# Dumptruck2018.net
KiCad netlist of a schematic drawn in EAGLE
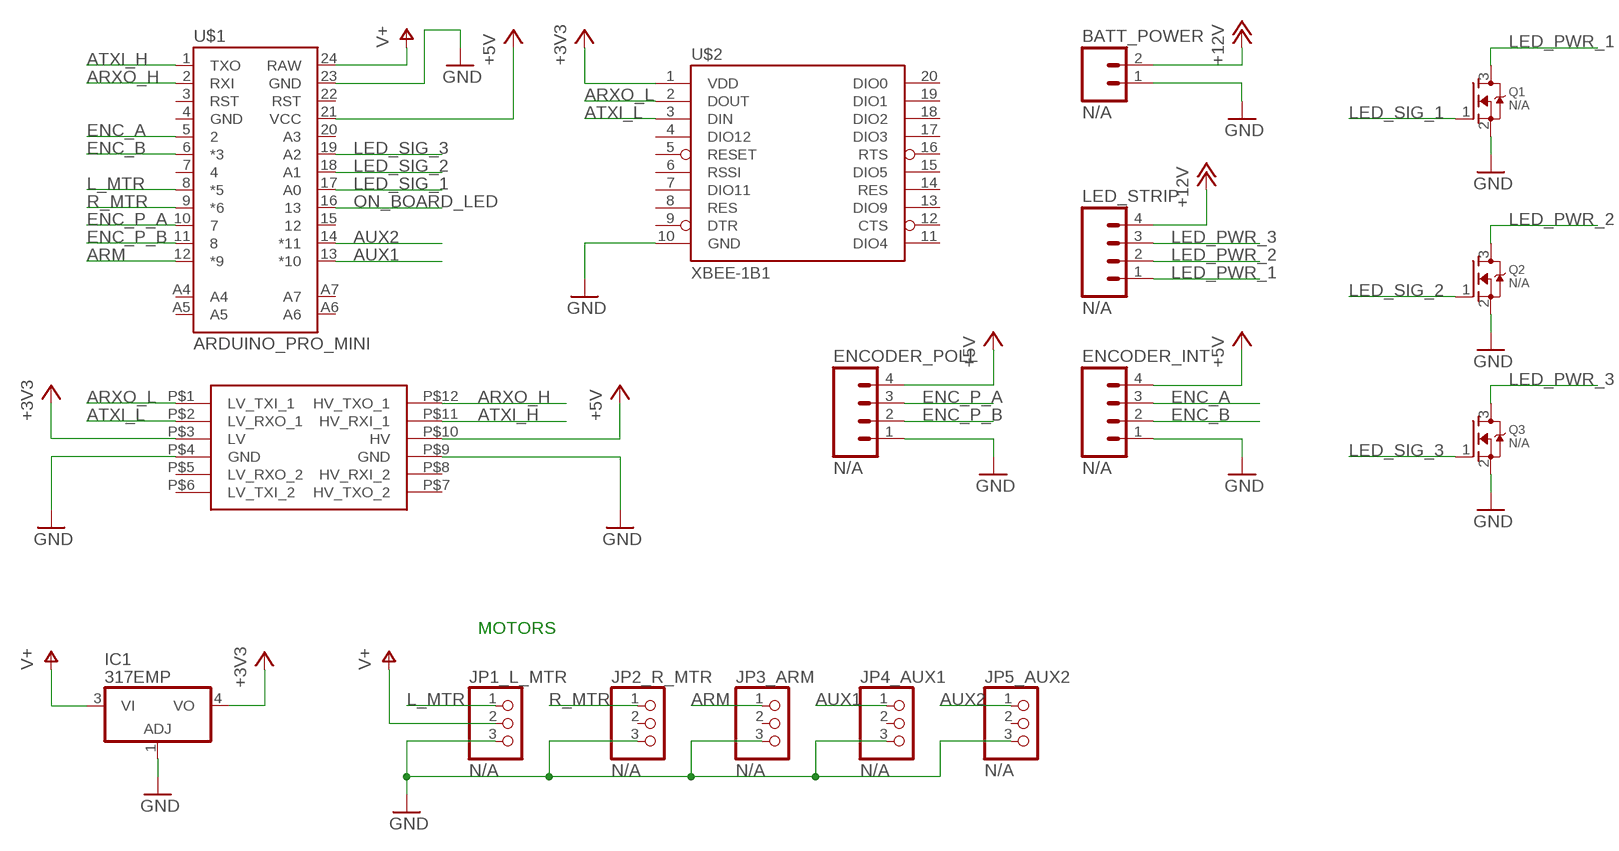
[diagram p0: schematic, sheet 1]

(export (version "E")
  (design (tool "Eeschema 10.0.6"))
  (components
    (comp (ref "BATT_POWER")
      (value "N/A")
      (footprint "eagle-import:1X02")
      (libsource (lib "eagle-import") (part "M02PTH"))
    )
    (comp (ref "ENCODER_INT")
      (value "N/A")
      (footprint "eagle-import:1X04_LOCK")
      (libsource (lib "eagle-import") (part "M04LOCK"))
    )
    (comp (ref "ENCODER_POLL")
      (value "N/A")
      (footprint "eagle-import:1X04_LOCK")
      (libsource (lib "eagle-import") (part "M04LOCK"))
    )
    (comp (ref "IC1")
      (value "317EMP")
      (footprint "eagle-import:SOT223")
      (libsource (lib "eagle-import") (part "317EMP"))
    )
    (comp (ref "JP1_L_MTR")
      (value "N/A")
      (footprint "eagle-import:1X03")
      (libsource (lib "eagle-import") (part "PINHD-1X3"))
    )
    (comp (ref "JP2_R_MTR")
      (value "N/A")
      (footprint "eagle-import:1X03")
      (libsource (lib "eagle-import") (part "PINHD-1X3"))
    )
    (comp (ref "JP3_ARM")
      (value "N/A")
      (footprint "eagle-import:1X03")
      (libsource (lib "eagle-import") (part "PINHD-1X3"))
    )
    (comp (ref "JP4_AUX1")
      (value "N/A")
      (footprint "eagle-import:1X03")
      (libsource (lib "eagle-import") (part "PINHD-1X3"))
    )
    (comp (ref "JP5_AUX2")
      (value "N/A")
      (footprint "eagle-import:1X03")
      (libsource (lib "eagle-import") (part "PINHD-1X3"))
    )
    (comp (ref "LED_STRIP")
      (value "N/A")
      (footprint "eagle-import:1X04_LOCK")
      (libsource (lib "eagle-import") (part "M04LOCK"))
    )
    (comp (ref "Q1")
      (value "N/A")
      (footprint "eagle-import:SOT23")
      (libsource (lib "eagle-import") (part "MOSFET-NREFLOW"))
    )
    (comp (ref "Q2")
      (value "N/A")
      (footprint "eagle-import:SOT23")
      (libsource (lib "eagle-import") (part "MOSFET-NREFLOW"))
    )
    (comp (ref "Q3")
      (value "N/A")
      (footprint "eagle-import:SOT23")
      (libsource (lib "eagle-import") (part "MOSFET-NREFLOW"))
    )
    (comp (ref "U$1")
      (value "ARDUINO_PRO_MINI")
      (footprint "eagle-import:ARDUINO_PRO_MINI")
      (libsource (lib "eagle-import") (part "ARDUINO_PRO_MINI"))
    )
    (comp (ref "U$2")
      (value "XBEE-1B1")
      (footprint "eagle-import:XBEE-1")
      (libsource (lib "eagle-import") (part "XBEE-1B1"))
    )
    (comp (ref "U$3")
      (value "LOGIC_LEVEL_CONVERTER")
      (footprint "eagle-import:LOGIC_LEVEL_CONVERTER")
      (libsource (lib "eagle-import") (part "LOGIC_LEVEL_CONVERTER"))
    )
  )
  (nets
    (net (code "1") (name "+3V3") (class "Default")
      (node (ref "IC1") (pin "4") (pinfunction "VO_4") (pintype "passive"))
      (node (ref "U$2") (pin "1") (pinfunction "VDD_1") (pintype "power_in"))
      (node (ref "U$3") (pin "P$3") (pinfunction "LV_P$3") (pintype "bidirectional"))
    )
    (net (code "2") (name "+5V") (class "Default")
      (node (ref "ENCODER_INT") (pin "4") (pinfunction "4_4") (pintype "passive"))
      (node (ref "ENCODER_POLL") (pin "4") (pinfunction "4_4") (pintype "passive"))
      (node (ref "U$1") (pin "21") (pinfunction "VCC_21") (pintype "bidirectional"))
      (node (ref "U$3") (pin "P$10") (pinfunction "HV_P$10") (pintype "bidirectional"))
    )
    (net (code "3") (name "+12V") (class "Default")
      (node (ref "BATT_POWER") (pin "2") (pinfunction "2_2") (pintype "passive"))
      (node (ref "LED_STRIP") (pin "4") (pinfunction "4_4") (pintype "passive"))
    )
    (net (code "4") (name "/ARM") (class "Default")
      (node (ref "JP3_ARM") (pin "1") (pinfunction "1_1") (pintype "passive"))
      (node (ref "U$1") (pin "12") (pinfunction "*9_12") (pintype "bidirectional"))
    )
    (net (code "5") (name "/ARXO_H") (class "Default")
      (node (ref "U$1") (pin "2") (pinfunction "RXI_2") (pintype "bidirectional"))
      (node (ref "U$3") (pin "P$12") (pinfunction "HV_TXO_1_P$12") (pintype "bidirectional"))
    )
    (net (code "6") (name "/ARXO_L") (class "Default")
      (node (ref "U$2") (pin "2") (pinfunction "DOUT_2") (pintype "output"))
      (node (ref "U$3") (pin "P$1") (pinfunction "LV_TXI_1_P$1") (pintype "bidirectional"))
    )
    (net (code "7") (name "/ATXI_H") (class "Default")
      (node (ref "U$1") (pin "1") (pinfunction "TXO_1") (pintype "bidirectional"))
      (node (ref "U$3") (pin "P$11") (pinfunction "HV_RXI_1_P$11") (pintype "bidirectional"))
    )
    (net (code "8") (name "/ATXI_L") (class "Default")
      (node (ref "U$2") (pin "3") (pinfunction "DIN_3") (pintype "input"))
      (node (ref "U$3") (pin "P$2") (pinfunction "LV_RXO_1_P$2") (pintype "bidirectional"))
    )
    (net (code "9") (name "/AUX1") (class "Default")
      (node (ref "JP4_AUX1") (pin "1") (pinfunction "1_1") (pintype "passive"))
      (node (ref "U$1") (pin "13") (pinfunction "*10_13") (pintype "bidirectional"))
    )
    (net (code "10") (name "/AUX2") (class "Default")
      (node (ref "JP5_AUX2") (pin "1") (pinfunction "1_1") (pintype "passive"))
      (node (ref "U$1") (pin "14") (pinfunction "*11_14") (pintype "bidirectional"))
    )
    (net (code "11") (name "/ENC_A") (class "Default")
      (node (ref "ENCODER_INT") (pin "3") (pinfunction "3_3") (pintype "passive"))
      (node (ref "U$1") (pin "5") (pinfunction "2_5") (pintype "bidirectional"))
    )
    (net (code "12") (name "/ENC_B") (class "Default")
      (node (ref "ENCODER_INT") (pin "2") (pinfunction "2_2") (pintype "passive"))
      (node (ref "U$1") (pin "6") (pinfunction "*3_6") (pintype "bidirectional"))
    )
    (net (code "13") (name "/ENC_P_A") (class "Default")
      (node (ref "ENCODER_POLL") (pin "3") (pinfunction "3_3") (pintype "passive"))
      (node (ref "U$1") (pin "10") (pinfunction "7_10") (pintype "bidirectional"))
    )
    (net (code "14") (name "/ENC_P_B") (class "Default")
      (node (ref "ENCODER_POLL") (pin "2") (pinfunction "2_2") (pintype "passive"))
      (node (ref "U$1") (pin "11") (pinfunction "8_11") (pintype "bidirectional"))
    )
    (net (code "15") (name "/LED_PWR_1") (class "Default")
      (node (ref "LED_STRIP") (pin "1") (pinfunction "1_1") (pintype "passive"))
      (node (ref "Q1") (pin "3") (pinfunction "D_3") (pintype "bidirectional"))
    )
    (net (code "16") (name "/LED_PWR_2") (class "Default")
      (node (ref "LED_STRIP") (pin "2") (pinfunction "2_2") (pintype "passive"))
      (node (ref "Q2") (pin "3") (pinfunction "D_3") (pintype "bidirectional"))
    )
    (net (code "17") (name "/LED_PWR_3") (class "Default")
      (node (ref "LED_STRIP") (pin "3") (pinfunction "3_3") (pintype "passive"))
      (node (ref "Q3") (pin "3") (pinfunction "D_3") (pintype "bidirectional"))
    )
    (net (code "18") (name "/LED_SIG_1") (class "Default")
      (node (ref "Q1") (pin "1") (pinfunction "G_1") (pintype "bidirectional"))
      (node (ref "U$1") (pin "17") (pinfunction "A0_17") (pintype "bidirectional"))
    )
    (net (code "19") (name "/LED_SIG_2") (class "Default")
      (node (ref "Q2") (pin "1") (pinfunction "G_1") (pintype "bidirectional"))
      (node (ref "U$1") (pin "18") (pinfunction "A1_18") (pintype "bidirectional"))
    )
    (net (code "20") (name "/LED_SIG_3") (class "Default")
      (node (ref "Q3") (pin "1") (pinfunction "G_1") (pintype "bidirectional"))
      (node (ref "U$1") (pin "19") (pinfunction "A2_19") (pintype "bidirectional"))
    )
    (net (code "21") (name "/L_MTR") (class "Default")
      (node (ref "JP1_L_MTR") (pin "1") (pinfunction "1_1") (pintype "passive"))
      (node (ref "U$1") (pin "8") (pinfunction "*5_8") (pintype "bidirectional"))
    )
    (net (code "22") (name "/ON_BOARD_LED") (class "Default")
      (node (ref "U$1") (pin "16") (pinfunction "13_16") (pintype "bidirectional"))
    )
    (net (code "23") (name "/R_MTR") (class "Default")
      (node (ref "JP2_R_MTR") (pin "1") (pinfunction "1_1") (pintype "passive"))
      (node (ref "U$1") (pin "9") (pinfunction "*6_9") (pintype "bidirectional"))
    )
    (net (code "24") (name "GND") (class "Default")
      (node (ref "BATT_POWER") (pin "1") (pinfunction "1_1") (pintype "passive"))
      (node (ref "ENCODER_INT") (pin "1") (pinfunction "1_1") (pintype "passive"))
      (node (ref "ENCODER_POLL") (pin "1") (pinfunction "1_1") (pintype "passive"))
      (node (ref "IC1") (pin "1") (pinfunction "ADJ_1") (pintype "input"))
      (node (ref "JP1_L_MTR") (pin "3") (pinfunction "3_3") (pintype "passive"))
      (node (ref "JP2_R_MTR") (pin "3") (pinfunction "3_3") (pintype "passive"))
      (node (ref "JP3_ARM") (pin "3") (pinfunction "3_3") (pintype "passive"))
      (node (ref "JP4_AUX1") (pin "3") (pinfunction "3_3") (pintype "passive"))
      (node (ref "JP5_AUX2") (pin "3") (pinfunction "3_3") (pintype "passive"))
      (node (ref "Q1") (pin "2") (pinfunction "S_2") (pintype "bidirectional"))
      (node (ref "Q2") (pin "2") (pinfunction "S_2") (pintype "bidirectional"))
      (node (ref "Q3") (pin "2") (pinfunction "S_2") (pintype "bidirectional"))
      (node (ref "U$1") (pin "23") (pinfunction "GND_23") (pintype "bidirectional"))
      (node (ref "U$2") (pin "10") (pinfunction "GND_10") (pintype "power_in"))
      (node (ref "U$3") (pin "P$4") (pinfunction "GND_P$4") (pintype "bidirectional"))
      (node (ref "U$3") (pin "P$9") (pinfunction "GND_P$9") (pintype "bidirectional"))
    )
    (net (code "25") (name "V+") (class "Default")
      (node (ref "IC1") (pin "3") (pinfunction "VI_3") (pintype "input"))
      (node (ref "JP1_L_MTR") (pin "2") (pinfunction "2_2") (pintype "passive"))
      (node (ref "U$1") (pin "24") (pinfunction "RAW_24") (pintype "bidirectional"))
    )
    (net (code "26") (name "unconnected-(JP2_R_MTR-Pad2)") (class "Default")
      (node (ref "JP2_R_MTR") (pin "2") (pinfunction "2_2") (pintype "passive"))
    )
    (net (code "27") (name "unconnected-(JP3_ARM-Pad2)") (class "Default")
      (node (ref "JP3_ARM") (pin "2") (pinfunction "2_2") (pintype "passive"))
    )
    (net (code "28") (name "unconnected-(JP4_AUX1-Pad2)") (class "Default")
      (node (ref "JP4_AUX1") (pin "2") (pinfunction "2_2") (pintype "passive"))
    )
    (net (code "29") (name "unconnected-(JP5_AUX2-Pad2)") (class "Default")
      (node (ref "JP5_AUX2") (pin "2") (pinfunction "2_2") (pintype "passive"))
    )
    (net (code "30") (name "unconnected-(U$1-4-Pad7)") (class "Default")
      (node (ref "U$1") (pin "7") (pinfunction "4_7") (pintype "bidirectional"))
    )
    (net (code "31") (name "unconnected-(U$1-12-Pad15)") (class "Default")
      (node (ref "U$1") (pin "15") (pinfunction "12_15") (pintype "bidirectional"))
    )
    (net (code "32") (name "unconnected-(U$1-A3-Pad20)") (class "Default")
      (node (ref "U$1") (pin "20") (pinfunction "A3_20") (pintype "bidirectional"))
    )
    (net (code "33") (name "unconnected-(U$1-GND-Pad4)") (class "Default")
      (node (ref "U$1") (pin "4") (pinfunction "GND_4") (pintype "bidirectional"))
    )
    (net (code "34") (name "unconnected-(U$1-PadA4)") (class "Default")
      (node (ref "U$1") (pin "A4") (pinfunction "A4_A4") (pintype "bidirectional"))
    )
    (net (code "35") (name "unconnected-(U$1-PadA5)") (class "Default")
      (node (ref "U$1") (pin "A5") (pinfunction "A5_A5") (pintype "bidirectional"))
    )
    (net (code "36") (name "unconnected-(U$1-PadA6)") (class "Default")
      (node (ref "U$1") (pin "A6") (pinfunction "A6_A6") (pintype "bidirectional"))
    )
    (net (code "37") (name "unconnected-(U$1-PadA7)") (class "Default")
      (node (ref "U$1") (pin "A7") (pinfunction "A7_A7") (pintype "bidirectional"))
    )
    (net (code "38") (name "unconnected-(U$1-RST-Pad3)") (class "Default")
      (node (ref "U$1") (pin "3") (pinfunction "RST_3") (pintype "bidirectional"))
    )
    (net (code "39") (name "unconnected-(U$1-RST-Pad22)") (class "Default")
      (node (ref "U$1") (pin "22") (pinfunction "RST_22") (pintype "bidirectional"))
    )
    (net (code "40") (name "unconnected-(U$2-CTS-Pad12)") (class "Default")
      (node (ref "U$2") (pin "12") (pinfunction "CTS_12") (pintype "output"))
    )
    (net (code "41") (name "unconnected-(U$2-DIO0-Pad20)") (class "Default")
      (node (ref "U$2") (pin "20") (pinfunction "DIO0_20") (pintype "bidirectional"))
    )
    (net (code "42") (name "unconnected-(U$2-DIO1-Pad19)") (class "Default")
      (node (ref "U$2") (pin "19") (pinfunction "DIO1_19") (pintype "bidirectional"))
    )
    (net (code "43") (name "unconnected-(U$2-DIO2-Pad18)") (class "Default")
      (node (ref "U$2") (pin "18") (pinfunction "DIO2_18") (pintype "bidirectional"))
    )
    (net (code "44") (name "unconnected-(U$2-DIO3-Pad17)") (class "Default")
      (node (ref "U$2") (pin "17") (pinfunction "DIO3_17") (pintype "bidirectional"))
    )
    (net (code "45") (name "unconnected-(U$2-DIO4-Pad11)") (class "Default")
      (node (ref "U$2") (pin "11") (pinfunction "DIO4_11") (pintype "bidirectional"))
    )
    (net (code "46") (name "unconnected-(U$2-DIO5-Pad15)") (class "Default")
      (node (ref "U$2") (pin "15") (pinfunction "DIO5_15") (pintype "bidirectional"))
    )
    (net (code "47") (name "unconnected-(U$2-DIO9-Pad13)") (class "Default")
      (node (ref "U$2") (pin "13") (pinfunction "DIO9_13") (pintype "bidirectional"))
    )
    (net (code "48") (name "unconnected-(U$2-DIO11-Pad7)") (class "Default")
      (node (ref "U$2") (pin "7") (pinfunction "DIO11_7") (pintype "bidirectional"))
    )
    (net (code "49") (name "unconnected-(U$2-DIO12-Pad4)") (class "Default")
      (node (ref "U$2") (pin "4") (pinfunction "DIO12_4") (pintype "bidirectional"))
    )
    (net (code "50") (name "unconnected-(U$2-DTR-Pad9)") (class "Default")
      (node (ref "U$2") (pin "9") (pinfunction "DTR_9") (pintype "bidirectional"))
    )
    (net (code "51") (name "unconnected-(U$2-RES-Pad8)") (class "Default")
      (node (ref "U$2") (pin "8") (pinfunction "RES_8") (pintype "bidirectional"))
    )
    (net (code "52") (name "unconnected-(U$2-RES-Pad14)") (class "Default")
      (node (ref "U$2") (pin "14") (pinfunction "RES_14") (pintype "bidirectional"))
    )
    (net (code "53") (name "unconnected-(U$2-RESET-Pad5)") (class "Default")
      (node (ref "U$2") (pin "5") (pinfunction "RESET_5") (pintype "input"))
    )
    (net (code "54") (name "unconnected-(U$2-RSSI-Pad6)") (class "Default")
      (node (ref "U$2") (pin "6") (pinfunction "RSSI_6") (pintype "bidirectional"))
    )
    (net (code "55") (name "unconnected-(U$2-RTS-Pad16)") (class "Default")
      (node (ref "U$2") (pin "16") (pinfunction "RTS_16") (pintype "input"))
    )
    (net (code "56") (name "unconnected-(U$3-HV_RXI_2-PadP$8)") (class "Default")
      (node (ref "U$3") (pin "P$8") (pinfunction "HV_RXI_2_P$8") (pintype "bidirectional"))
    )
    (net (code "57") (name "unconnected-(U$3-HV_TXO_2-PadP$7)") (class "Default")
      (node (ref "U$3") (pin "P$7") (pinfunction "HV_TXO_2_P$7") (pintype "bidirectional"))
    )
    (net (code "58") (name "unconnected-(U$3-LV_RXO_2-PadP$5)") (class "Default")
      (node (ref "U$3") (pin "P$5") (pinfunction "LV_RXO_2_P$5") (pintype "bidirectional"))
    )
    (net (code "59") (name "unconnected-(U$3-LV_TXI_2-PadP$6)") (class "Default")
      (node (ref "U$3") (pin "P$6") (pinfunction "LV_TXI_2_P$6") (pintype "bidirectional"))
    )
  )
)
